# TouScruino-ui2_IL-v0.net
KiCad netlist of a schematic drawn in EAGLE
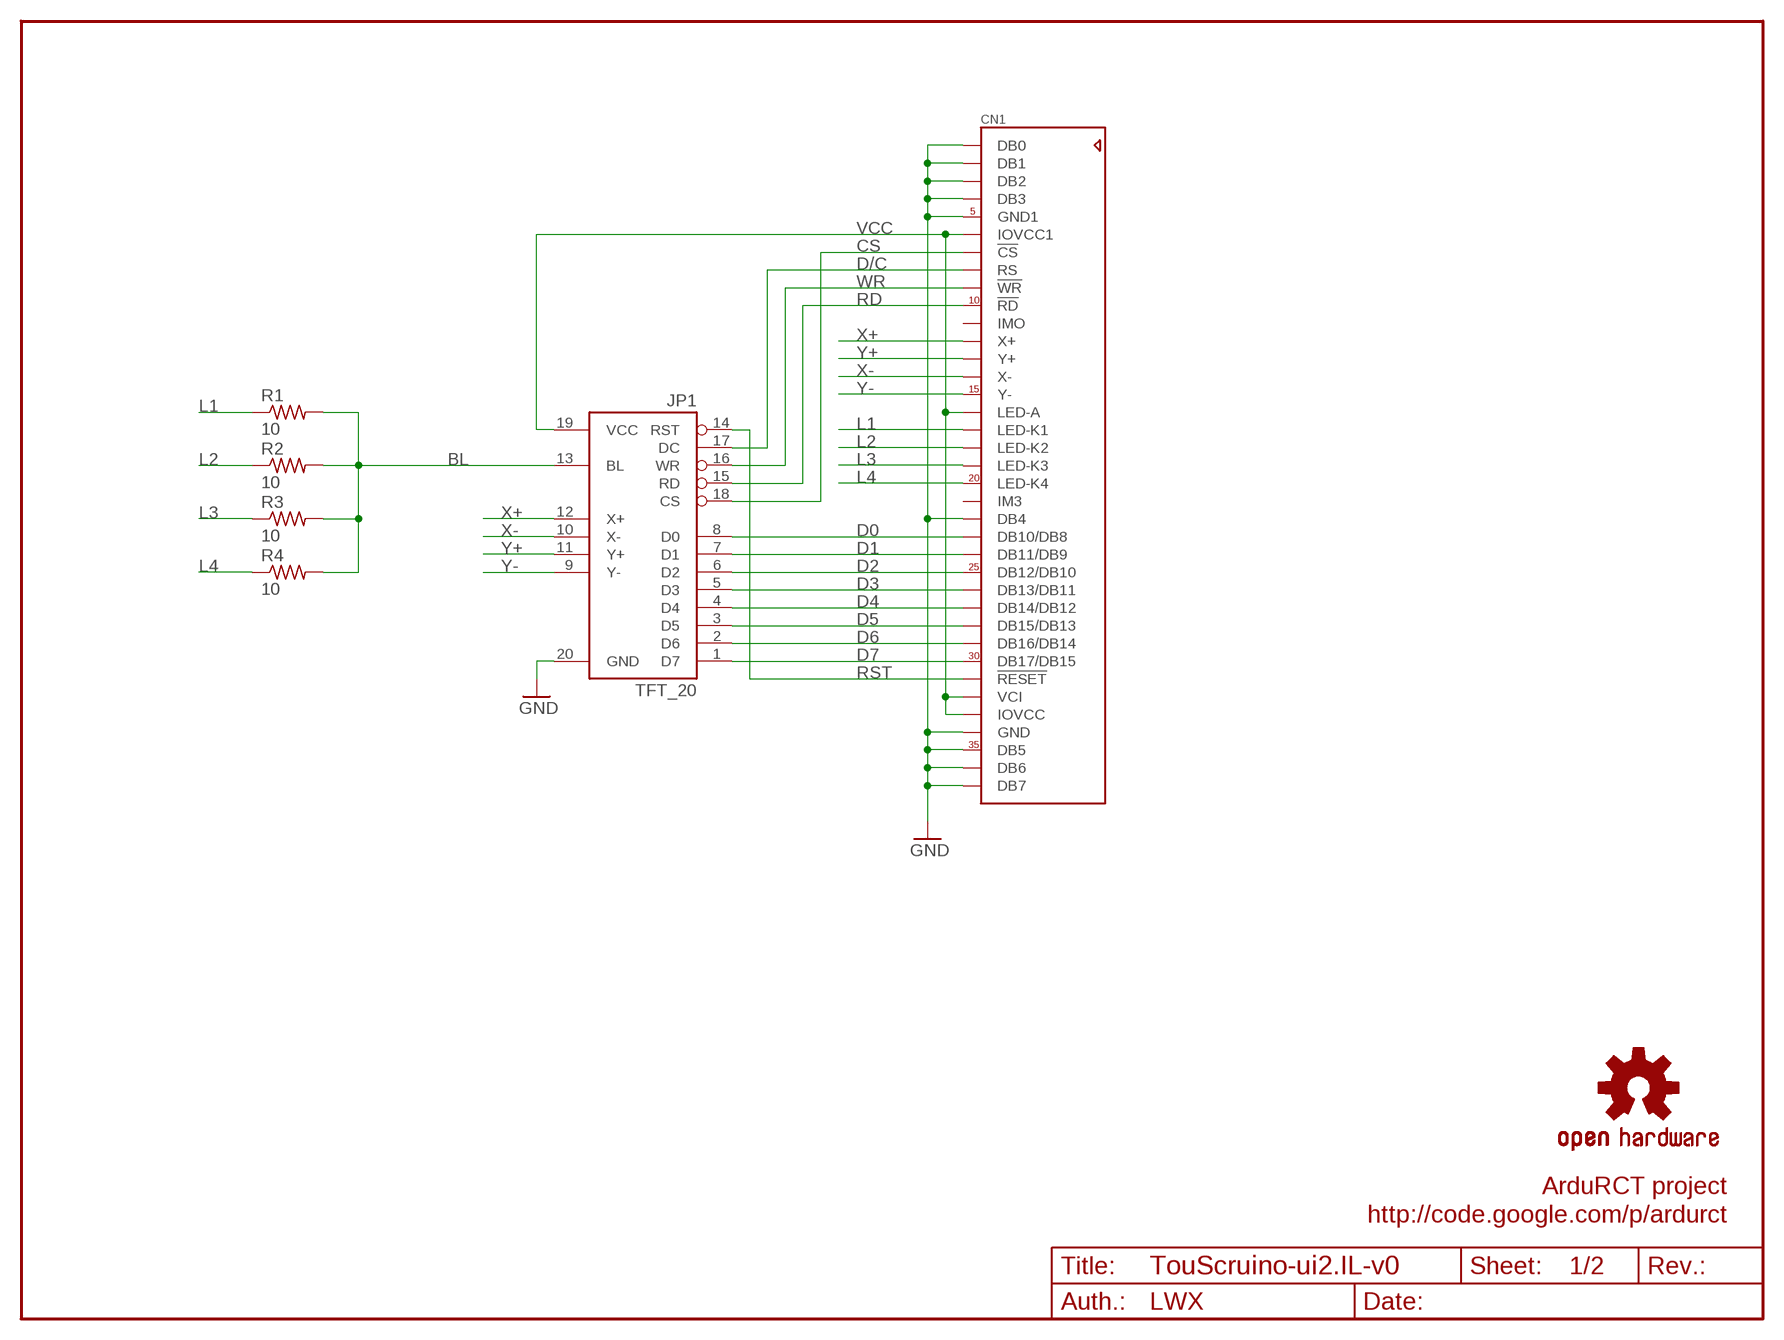
[diagram p0: schematic, sheet 1]

(export (version "E")
  (design (tool "Eeschema 10.0.6"))
  (components
    (comp (ref "CN1")
      (value "ILI9325_LCD1.0MM")
      (footprint "eagle-import:ILI9325_28INCH_TS")
      (libsource (lib "eagle-import") (part "ILI9325_LCD1.0MM"))
    )
    (comp (ref "JP1")
      (value "TFT_20")
      (footprint "eagle-import:TFT_20")
      (libsource (lib "eagle-import") (part "TFT_20"))
    )
    (comp (ref "R1")
      (value "10")
      (footprint "eagle-import:R0603")
      (libsource (lib "eagle-import") (part "R-US_R0603"))
    )
    (comp (ref "R2")
      (value "10")
      (footprint "eagle-import:R0603")
      (libsource (lib "eagle-import") (part "R-US_R0603"))
    )
    (comp (ref "R3")
      (value "10")
      (footprint "eagle-import:R0603")
      (libsource (lib "eagle-import") (part "R-US_R0603"))
    )
    (comp (ref "R4")
      (value "10")
      (footprint "eagle-import:R0603")
      (libsource (lib "eagle-import") (part "R-US_R0603"))
    )
    (comp (ref "U$3")
      (value "OSHW-LOGOM")
      (footprint "eagle-import:OSHW-LOGO-M")
      (libsource (lib "eagle-import") (part "OSHW-LOGOM"))
    )
  )
  (nets
    (net (code "1") (name "/BL") (class "Default")
      (node (ref "JP1") (pin "13") (pinfunction "BL_13") (pintype "bidirectional"))
      (node (ref "R1") (pin "2") (pinfunction "2_2") (pintype "passive"))
      (node (ref "R2") (pin "2") (pinfunction "2_2") (pintype "passive"))
      (node (ref "R3") (pin "2") (pinfunction "2_2") (pintype "passive"))
      (node (ref "R4") (pin "2") (pinfunction "2_2") (pintype "passive"))
    )
    (net (code "2") (name "/CS") (class "Default")
      (node (ref "CN1") (pin "7") (pinfunction "~{CS}_7") (pintype "passive"))
      (node (ref "JP1") (pin "18") (pinfunction "CS_18") (pintype "bidirectional"))
    )
    (net (code "3") (name "/D0") (class "Default")
      (node (ref "CN1") (pin "23") (pinfunction "DB10/DB8_23") (pintype "passive"))
      (node (ref "JP1") (pin "8") (pinfunction "D0_8") (pintype "bidirectional"))
    )
    (net (code "4") (name "/D1") (class "Default")
      (node (ref "CN1") (pin "24") (pinfunction "DB11/DB9_24") (pintype "passive"))
      (node (ref "JP1") (pin "7") (pinfunction "D1_7") (pintype "bidirectional"))
    )
    (net (code "5") (name "/D2") (class "Default")
      (node (ref "CN1") (pin "25") (pinfunction "DB12/DB10_25") (pintype "passive"))
      (node (ref "JP1") (pin "6") (pinfunction "D2_6") (pintype "bidirectional"))
    )
    (net (code "6") (name "/D3") (class "Default")
      (node (ref "CN1") (pin "26") (pinfunction "DB13/DB11_26") (pintype "passive"))
      (node (ref "JP1") (pin "5") (pinfunction "D3_5") (pintype "bidirectional"))
    )
    (net (code "7") (name "/D4") (class "Default")
      (node (ref "CN1") (pin "27") (pinfunction "DB14/DB12_27") (pintype "passive"))
      (node (ref "JP1") (pin "4") (pinfunction "D4_4") (pintype "bidirectional"))
    )
    (net (code "8") (name "/D5") (class "Default")
      (node (ref "CN1") (pin "28") (pinfunction "DB15/DB13_28") (pintype "passive"))
      (node (ref "JP1") (pin "3") (pinfunction "D5_3") (pintype "bidirectional"))
    )
    (net (code "9") (name "/D6") (class "Default")
      (node (ref "CN1") (pin "29") (pinfunction "DB16/DB14_29") (pintype "passive"))
      (node (ref "JP1") (pin "2") (pinfunction "D6_2") (pintype "bidirectional"))
    )
    (net (code "10") (name "/D7") (class "Default")
      (node (ref "CN1") (pin "30") (pinfunction "DB17/DB15_30") (pintype "passive"))
      (node (ref "JP1") (pin "1") (pinfunction "D7_1") (pintype "bidirectional"))
    )
    (net (code "11") (name "/D{slash}C") (class "Default")
      (node (ref "CN1") (pin "8") (pinfunction "RS_8") (pintype "passive"))
      (node (ref "JP1") (pin "17") (pinfunction "DC_17") (pintype "bidirectional"))
    )
    (net (code "12") (name "/L1") (class "Default")
      (node (ref "CN1") (pin "17") (pinfunction "LED-K1_17") (pintype "passive"))
      (node (ref "R1") (pin "1") (pinfunction "1_1") (pintype "passive"))
    )
    (net (code "13") (name "/L2") (class "Default")
      (node (ref "CN1") (pin "18") (pinfunction "LED-K2_18") (pintype "passive"))
      (node (ref "R2") (pin "1") (pinfunction "1_1") (pintype "passive"))
    )
    (net (code "14") (name "/L3") (class "Default")
      (node (ref "CN1") (pin "19") (pinfunction "LED-K3_19") (pintype "passive"))
      (node (ref "R3") (pin "1") (pinfunction "1_1") (pintype "passive"))
    )
    (net (code "15") (name "/L4") (class "Default")
      (node (ref "CN1") (pin "20") (pinfunction "LED-K4_20") (pintype "passive"))
      (node (ref "R4") (pin "1") (pinfunction "1_1") (pintype "passive"))
    )
    (net (code "16") (name "/RD") (class "Default")
      (node (ref "CN1") (pin "10") (pinfunction "~{RD}_10") (pintype "passive"))
      (node (ref "JP1") (pin "15") (pinfunction "RD_15") (pintype "bidirectional"))
    )
    (net (code "17") (name "/RST") (class "Default")
      (node (ref "CN1") (pin "31") (pinfunction "~{RESET}_31") (pintype "passive"))
      (node (ref "JP1") (pin "14") (pinfunction "RST_14") (pintype "bidirectional"))
    )
    (net (code "18") (name "/VCC") (class "Default")
      (node (ref "CN1") (pin "16") (pinfunction "LED-A_16") (pintype "passive"))
      (node (ref "CN1") (pin "32") (pinfunction "VCI_32") (pintype "power_in"))
      (node (ref "CN1") (pin "33") (pinfunction "IOVCC_33") (pintype "power_in"))
      (node (ref "CN1") (pin "6") (pinfunction "IOVCC1_6") (pintype "power_in"))
      (node (ref "JP1") (pin "19") (pinfunction "VCC_19") (pintype "bidirectional"))
    )
    (net (code "19") (name "/WR") (class "Default")
      (node (ref "CN1") (pin "9") (pinfunction "~{WR}_9") (pintype "passive"))
      (node (ref "JP1") (pin "16") (pinfunction "WR_16") (pintype "bidirectional"))
    )
    (net (code "20") (name "/X+") (class "Default")
      (node (ref "CN1") (pin "12") (pinfunction "X+_12") (pintype "passive"))
      (node (ref "JP1") (pin "12") (pinfunction "X+_12") (pintype "bidirectional"))
    )
    (net (code "21") (name "/X-") (class "Default")
      (node (ref "CN1") (pin "14") (pinfunction "X-_14") (pintype "passive"))
      (node (ref "JP1") (pin "10") (pinfunction "X-_10") (pintype "bidirectional"))
    )
    (net (code "22") (name "/Y+") (class "Default")
      (node (ref "CN1") (pin "13") (pinfunction "Y+_13") (pintype "passive"))
      (node (ref "JP1") (pin "11") (pinfunction "Y+_11") (pintype "bidirectional"))
    )
    (net (code "23") (name "/Y-") (class "Default")
      (node (ref "CN1") (pin "15") (pinfunction "Y-_15") (pintype "passive"))
      (node (ref "JP1") (pin "9") (pinfunction "Y-_9") (pintype "bidirectional"))
    )
    (net (code "24") (name "GND") (class "Default")
      (node (ref "CN1") (pin "1") (pinfunction "DB0_1") (pintype "passive"))
      (node (ref "CN1") (pin "2") (pinfunction "DB1_2") (pintype "passive"))
      (node (ref "CN1") (pin "22") (pinfunction "DB4_22") (pintype "passive"))
      (node (ref "CN1") (pin "3") (pinfunction "DB2_3") (pintype "passive"))
      (node (ref "CN1") (pin "34") (pinfunction "GND_34") (pintype "power_in"))
      (node (ref "CN1") (pin "35") (pinfunction "DB5_35") (pintype "passive"))
      (node (ref "CN1") (pin "36") (pinfunction "DB6_36") (pintype "passive"))
      (node (ref "CN1") (pin "37") (pinfunction "DB7_37") (pintype "passive"))
      (node (ref "CN1") (pin "4") (pinfunction "DB3_4") (pintype "passive"))
      (node (ref "CN1") (pin "5") (pinfunction "GND1_5") (pintype "power_in"))
      (node (ref "JP1") (pin "20") (pinfunction "GND_20") (pintype "bidirectional"))
    )
    (net (code "25") (name "unconnected-(CN1-IM3-Pad21)") (class "Default")
      (node (ref "CN1") (pin "21") (pinfunction "IM3_21") (pintype "passive"))
    )
    (net (code "26") (name "unconnected-(CN1-IMO-Pad11)") (class "Default")
      (node (ref "CN1") (pin "11") (pinfunction "IMO_11") (pintype "passive"))
    )
  )
)
